# USB_Isolator.net
KiCad netlist of a schematic drawn in EAGLE
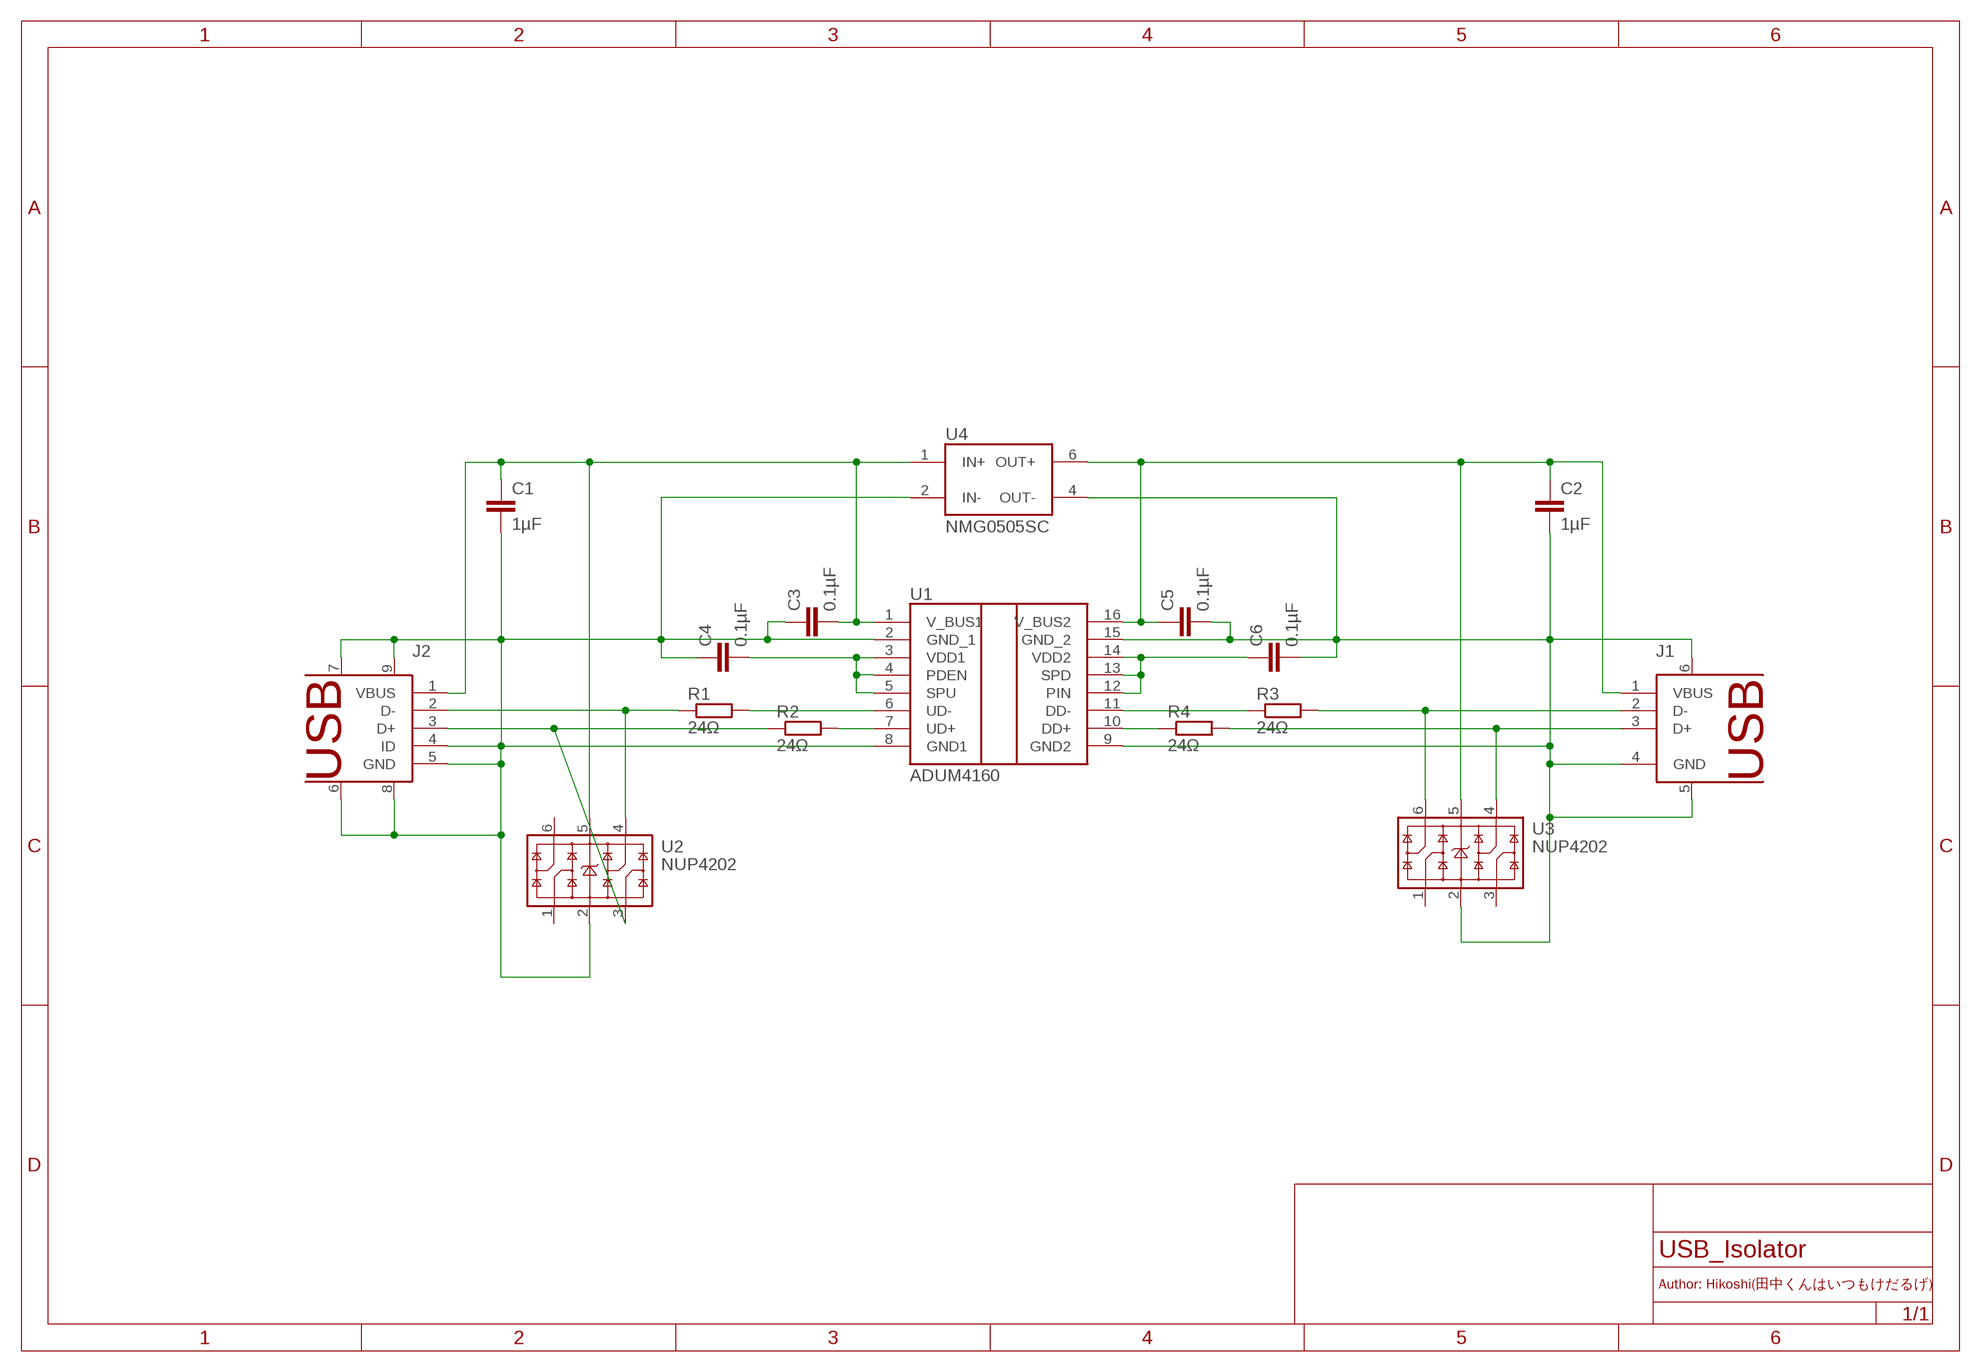
[diagram p0: schematic, sheet 1]

(export (version "E")
  (design (tool "Eeschema 10.0.6"))
  (components
    (comp (ref "C1")
      (value "1µF")
      (footprint "eagle-import:C0805")
      (libsource (lib "eagle-import") (part "CAPACITOR0805"))
    )
    (comp (ref "C2")
      (value "1µF")
      (footprint "eagle-import:C0805")
      (libsource (lib "eagle-import") (part "CAPACITOR0805"))
    )
    (comp (ref "C3")
      (value "0.1µF")
      (footprint "eagle-import:C0402")
      (libsource (lib "eagle-import") (part "CAPACITOR0402"))
    )
    (comp (ref "C4")
      (value "0.1µF")
      (footprint "eagle-import:C0402")
      (libsource (lib "eagle-import") (part "CAPACITOR0402"))
    )
    (comp (ref "C5")
      (value "0.1µF")
      (footprint "eagle-import:C0402")
      (libsource (lib "eagle-import") (part "CAPACITOR0402"))
    )
    (comp (ref "C6")
      (value "0.1µF")
      (footprint "eagle-import:C0402")
      (libsource (lib "eagle-import") (part "CAPACITOR0402"))
    )
    (comp (ref "J1")
      (value "USB_A")
      (footprint "eagle-import:USB_A_F")
      (libsource (lib "eagle-import") (part "USB_A"))
    )
    (comp (ref "J2")
      (value "USB_MINI")
      (footprint "eagle-import:USB_MINI")
      (libsource (lib "eagle-import") (part "USB_MINI"))
    )
    (comp (ref "R1")
      (value "24Ω")
      (footprint "eagle-import:R0402")
      (libsource (lib "eagle-import") (part "RESISTOR0402"))
    )
    (comp (ref "R2")
      (value "24Ω")
      (footprint "eagle-import:R0402")
      (libsource (lib "eagle-import") (part "RESISTOR0402"))
    )
    (comp (ref "R3")
      (value "24Ω")
      (footprint "eagle-import:R0402")
      (libsource (lib "eagle-import") (part "RESISTOR0402"))
    )
    (comp (ref "R4")
      (value "24Ω")
      (footprint "eagle-import:R0402")
      (libsource (lib "eagle-import") (part "RESISTOR0402"))
    )
    (comp (ref "U1")
      (value "ADUM4160")
      (footprint "eagle-import:SOIC_W-28")
      (libsource (lib "eagle-import") (part "ADUM4160"))
    )
    (comp (ref "U2")
      (value "NUP4202")
      (footprint "eagle-import:SOT-363")
      (libsource (lib "eagle-import") (part "NUP4202"))
    )
    (comp (ref "U3")
      (value "NUP4202")
      (footprint "eagle-import:SOT-363")
      (libsource (lib "eagle-import") (part "NUP4202"))
    )
    (comp (ref "U4")
      (value "NMG0505SC")
      (footprint "eagle-import:NMG")
      (libsource (lib "eagle-import") (part "NMG0505SC"))
    )
  )
  (nets
    (net (code "1") (name "Net-(J1-D+)") (class "Default")
      (node (ref "J1") (pin "3") (pinfunction "D+_3") (pintype "bidirectional"))
      (node (ref "R4") (pin "2") (pinfunction "2_2") (pintype "passive"))
      (node (ref "U3") (pin "4") (pinfunction "IO4_4") (pintype "bidirectional"))
    )
    (net (code "2") (name "Net-(J1-D-)") (class "Default")
      (node (ref "J1") (pin "2") (pinfunction "D-_2") (pintype "bidirectional"))
      (node (ref "R3") (pin "2") (pinfunction "2_2") (pintype "passive"))
      (node (ref "U3") (pin "6") (pinfunction "IO6_6") (pintype "bidirectional"))
    )
    (net (code "3") (name "Net-(J1-GND)") (class "Default")
      (node (ref "C2") (pin "2") (pinfunction "2_2") (pintype "passive"))
      (node (ref "C5") (pin "2") (pinfunction "2_2") (pintype "passive"))
      (node (ref "C6") (pin "2") (pinfunction "2_2") (pintype "passive"))
      (node (ref "J1") (pin "4") (pinfunction "GND_4") (pintype "power_in"))
      (node (ref "J1") (pin "5") (pinfunction "SHIELD1_5") (pintype "power_in"))
      (node (ref "J1") (pin "6") (pinfunction "SHIELD2_6") (pintype "power_in"))
      (node (ref "U1") (pin "15") (pinfunction "GND_2_15") (pintype "power_in"))
      (node (ref "U1") (pin "9") (pinfunction "GND2_9") (pintype "power_in"))
      (node (ref "U3") (pin "2") (pinfunction "VN_2") (pintype "power_in"))
      (node (ref "U4") (pin "4") (pinfunction "OUT-_4") (pintype "power_in"))
    )
    (net (code "4") (name "Net-(J1-VBUS)") (class "Default")
      (node (ref "C2") (pin "1") (pinfunction "1_1") (pintype "passive"))
      (node (ref "C5") (pin "1") (pinfunction "1_1") (pintype "passive"))
      (node (ref "J1") (pin "1") (pinfunction "VBUS_1") (pintype "power_in"))
      (node (ref "U1") (pin "16") (pinfunction "V_BUS2_16") (pintype "power_in"))
      (node (ref "U3") (pin "5") (pinfunction "VP_5") (pintype "power_in"))
      (node (ref "U4") (pin "6") (pinfunction "OUT+_6") (pintype "power_in"))
    )
    (net (code "5") (name "Net-(J2-D+)") (class "Default")
      (node (ref "J2") (pin "3") (pinfunction "D+_3") (pintype "bidirectional"))
      (node (ref "R2") (pin "1") (pinfunction "1_1") (pintype "passive"))
      (node (ref "U2") (pin "3") (pinfunction "IO3_3") (pintype "bidirectional"))
    )
    (net (code "6") (name "Net-(J2-D-)") (class "Default")
      (node (ref "J2") (pin "2") (pinfunction "D-_2") (pintype "bidirectional"))
      (node (ref "R1") (pin "1") (pinfunction "1_1") (pintype "passive"))
      (node (ref "U2") (pin "4") (pinfunction "IO4_4") (pintype "bidirectional"))
    )
    (net (code "7") (name "Net-(J2-GND)") (class "Default")
      (node (ref "C1") (pin "2") (pinfunction "2_2") (pintype "passive"))
      (node (ref "C3") (pin "1") (pinfunction "1_1") (pintype "passive"))
      (node (ref "C4") (pin "1") (pinfunction "1_1") (pintype "passive"))
      (node (ref "J2") (pin "4") (pinfunction "ID_4") (pintype "bidirectional"))
      (node (ref "J2") (pin "5") (pinfunction "GND_5") (pintype "power_in"))
      (node (ref "J2") (pin "6") (pinfunction "SHIELD1_6") (pintype "power_in"))
      (node (ref "J2") (pin "7") (pinfunction "SHIELD2_7") (pintype "power_in"))
      (node (ref "J2") (pin "8") (pinfunction "SHIELD3_8") (pintype "power_in"))
      (node (ref "J2") (pin "9") (pinfunction "SHIELD4_9") (pintype "power_in"))
      (node (ref "U1") (pin "2") (pinfunction "GND_1_2") (pintype "power_in"))
      (node (ref "U1") (pin "8") (pinfunction "GND1_8") (pintype "power_in"))
      (node (ref "U2") (pin "2") (pinfunction "VN_2") (pintype "power_in"))
      (node (ref "U4") (pin "2") (pinfunction "IN-_2") (pintype "power_in"))
    )
    (net (code "8") (name "Net-(J2-VBUS)") (class "Default")
      (node (ref "C1") (pin "1") (pinfunction "1_1") (pintype "passive"))
      (node (ref "C3") (pin "2") (pinfunction "2_2") (pintype "passive"))
      (node (ref "J2") (pin "1") (pinfunction "VBUS_1") (pintype "bidirectional"))
      (node (ref "U1") (pin "1") (pinfunction "V_BUS1_1") (pintype "power_in"))
      (node (ref "U2") (pin "5") (pinfunction "VP_5") (pintype "power_in"))
      (node (ref "U4") (pin "1") (pinfunction "IN+_1") (pintype "power_in"))
    )
    (net (code "9") (name "Net-(U1-DD+)") (class "Default")
      (node (ref "R4") (pin "1") (pinfunction "1_1") (pintype "passive"))
      (node (ref "U1") (pin "10") (pinfunction "DD+_10") (pintype "bidirectional"))
    )
    (net (code "10") (name "Net-(U1-DD-)") (class "Default")
      (node (ref "R3") (pin "1") (pinfunction "1_1") (pintype "passive"))
      (node (ref "U1") (pin "11") (pinfunction "DD-_11") (pintype "bidirectional"))
    )
    (net (code "11") (name "Net-(U1-PDEN)") (class "Default")
      (node (ref "C4") (pin "2") (pinfunction "2_2") (pintype "passive"))
      (node (ref "U1") (pin "3") (pinfunction "VDD1_3") (pintype "power_in"))
      (node (ref "U1") (pin "4") (pinfunction "PDEN_4") (pintype "input"))
      (node (ref "U1") (pin "5") (pinfunction "SPU_5") (pintype "input"))
    )
    (net (code "12") (name "Net-(U1-PIN)") (class "Default")
      (node (ref "C6") (pin "1") (pinfunction "1_1") (pintype "passive"))
      (node (ref "U1") (pin "12") (pinfunction "PIN_12") (pintype "input"))
      (node (ref "U1") (pin "13") (pinfunction "SPD_13") (pintype "input"))
      (node (ref "U1") (pin "14") (pinfunction "VDD2_14") (pintype "power_in"))
    )
    (net (code "13") (name "Net-(U1-UD+)") (class "Default")
      (node (ref "R2") (pin "2") (pinfunction "2_2") (pintype "passive"))
      (node (ref "U1") (pin "7") (pinfunction "UD+_7") (pintype "bidirectional"))
    )
    (net (code "14") (name "Net-(U1-UD-)") (class "Default")
      (node (ref "R1") (pin "2") (pinfunction "2_2") (pintype "passive"))
      (node (ref "U1") (pin "6") (pinfunction "UD-_6") (pintype "bidirectional"))
    )
    (net (code "15") (name "unconnected-(U2-IO1-Pad1)") (class "Default")
      (node (ref "U2") (pin "1") (pinfunction "IO1_1") (pintype "bidirectional"))
    )
    (net (code "16") (name "unconnected-(U2-IO6-Pad6)") (class "Default")
      (node (ref "U2") (pin "6") (pinfunction "IO6_6") (pintype "bidirectional"))
    )
    (net (code "17") (name "unconnected-(U3-IO1-Pad1)") (class "Default")
      (node (ref "U3") (pin "1") (pinfunction "IO1_1") (pintype "bidirectional"))
    )
    (net (code "18") (name "unconnected-(U3-IO3-Pad3)") (class "Default")
      (node (ref "U3") (pin "3") (pinfunction "IO3_3") (pintype "bidirectional"))
    )
  )
)
